# MicroSD-BoosterPack-RevA1.net
KiCad netlist of a schematic drawn in EAGLE
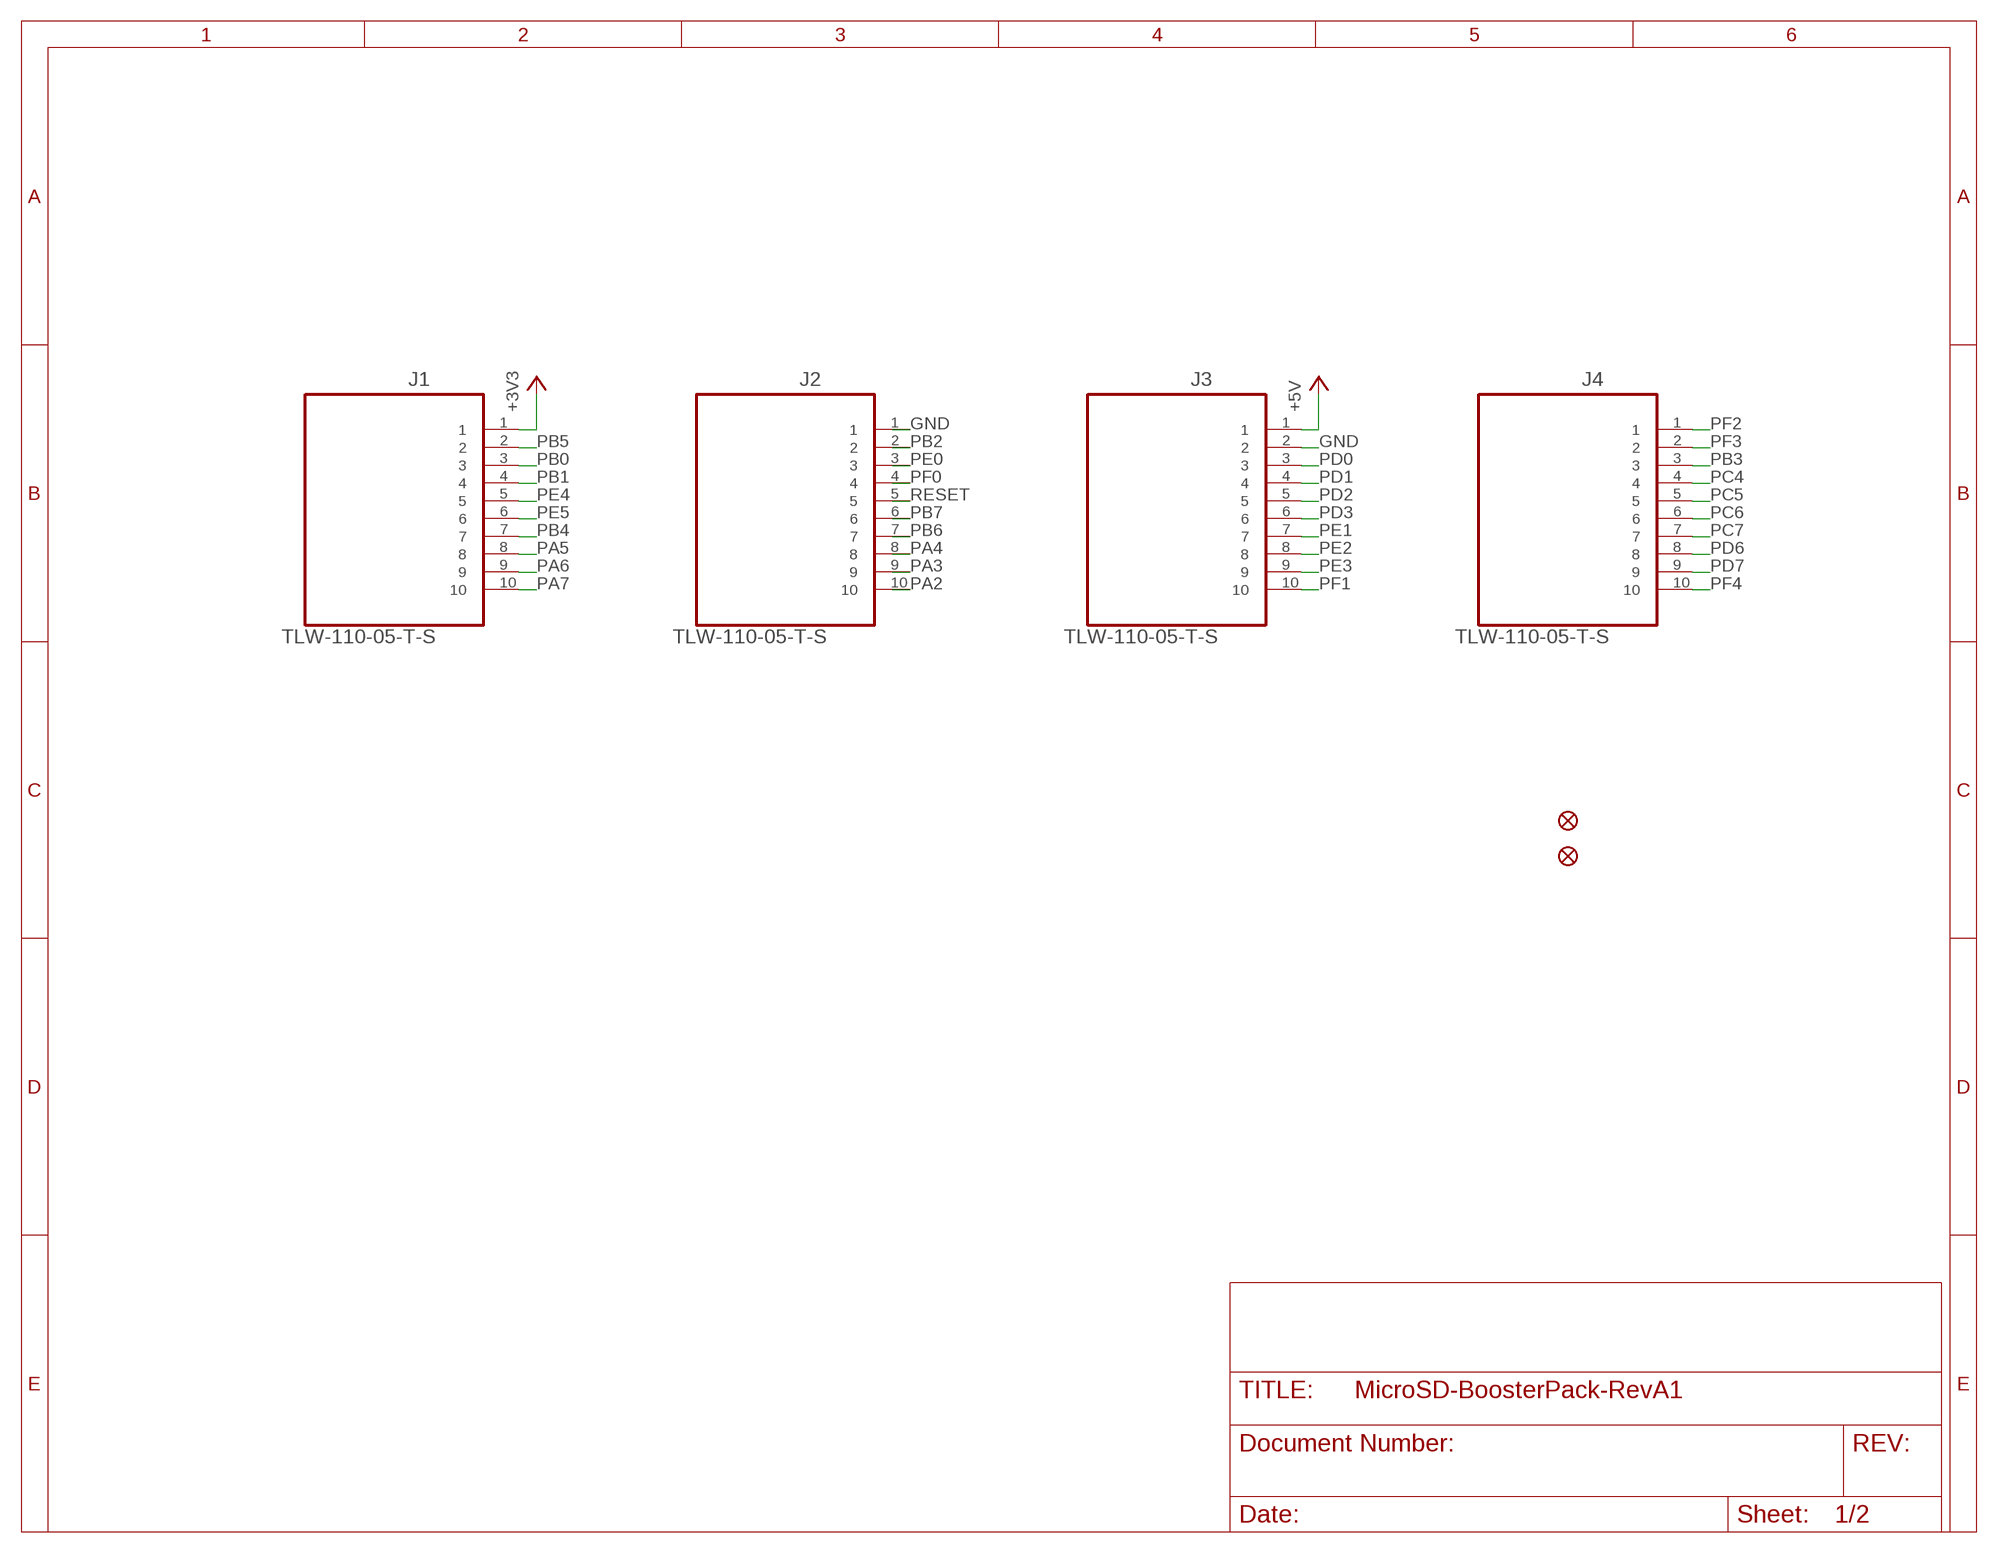
[diagram p0: schematic, sheet 1]
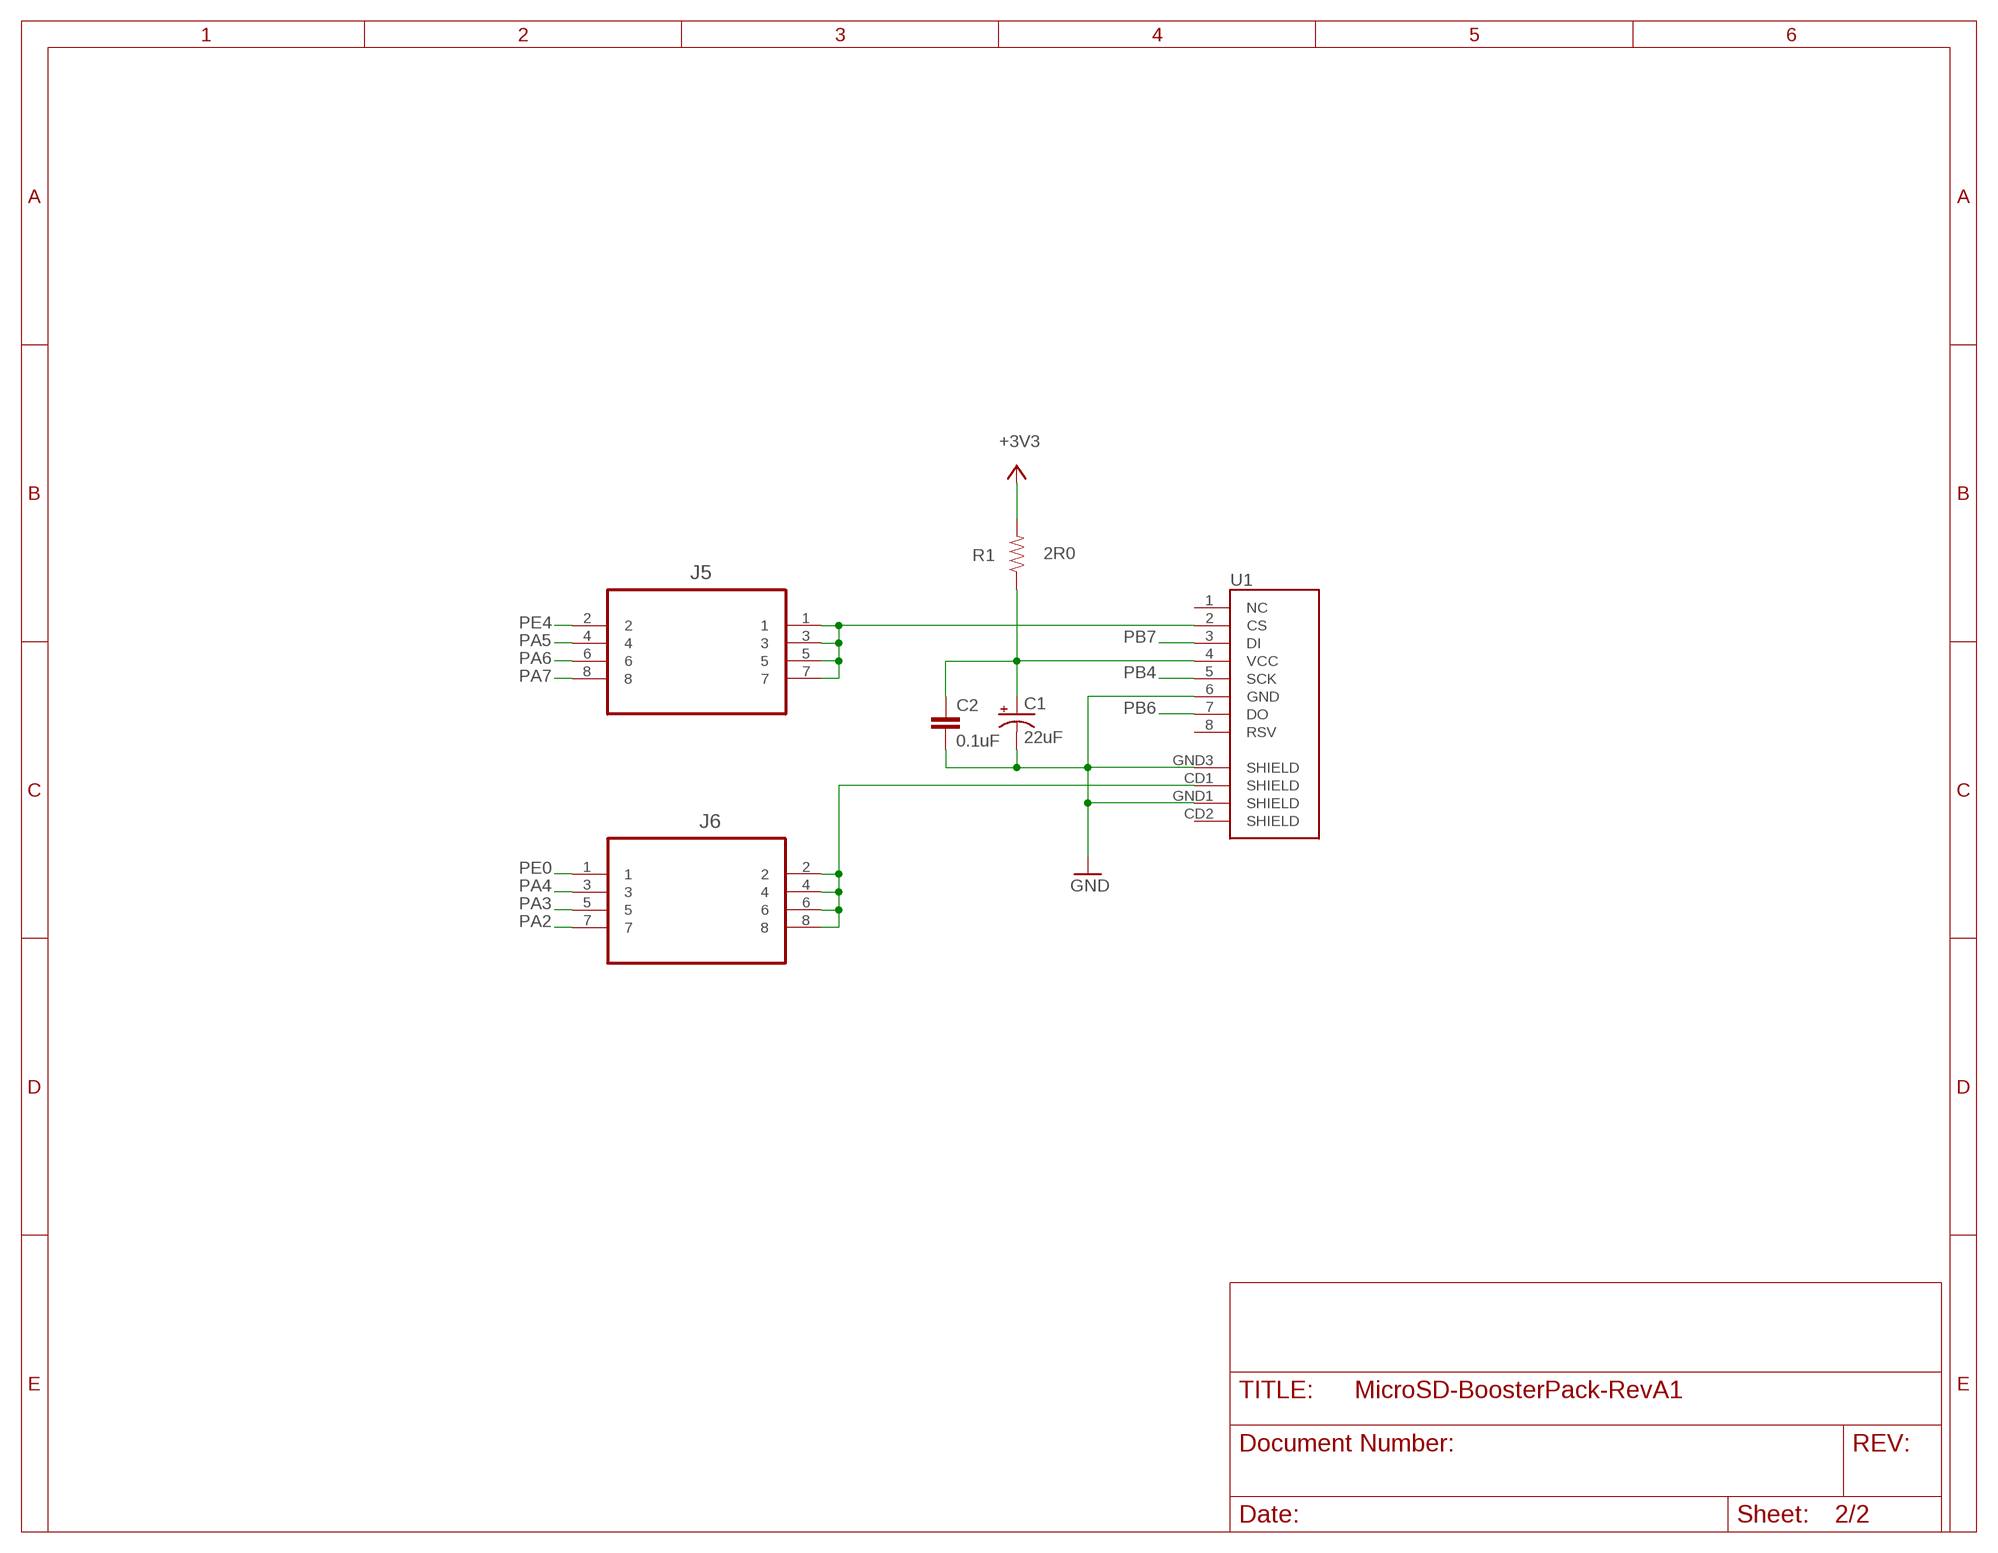
[diagram p1: schematic, sheet 2]

(export (version "E")
  (design (tool "Eeschema 10.0.6"))
  (components
    (comp (ref "C1")
      (value "22uF")
      (footprint "eagle-import:EIA3216")
      (libsource (lib "eagle-import") (part "10UF-16V-10%(TANT)"))
    )
    (comp (ref "C2")
      (value "0.1uF")
      (footprint "eagle-import:0603-CAP")
      (libsource (lib "eagle-import") (part "CAP0603-CAP"))
    )
    (comp (ref "J5")
      (value "SLW-104-01-T-D")
      (footprint "eagle-import:SAMTEC_SLW-104-01-T-D")
      (libsource (lib "eagle-import") (part "SLW-104-01-T-D"))
    )
    (comp (ref "J6")
      (value "SLW-104-01-T-D")
      (footprint "eagle-import:SAMTEC_SLW-104-01-T-D")
      (libsource (lib "eagle-import") (part "SLW-104-01-T-D"))
    )
    (comp (ref "R1")
      (value "2R0")
      (footprint "eagle-import:0603-RES")
      (libsource (lib "eagle-import") (part "RESISTOR0603-RES"))
    )
    (comp (ref "U1")
      (value "USD-SOCKETNEW")
      (footprint "eagle-import:MICRO-SD-SOCKET-PP")
      (libsource (lib "eagle-import") (part "USD-SOCKETNEW"))
    )
    (comp (ref "FID1")
      (value "FIDUCIAL1X2")
      (footprint "eagle-import:FIDUCIAL-1X2")
      (libsource (lib "eagle-import") (part "FIDUCIAL1X2"))
    )
    (comp (ref "FID2")
      (value "FIDUCIAL1X2")
      (footprint "eagle-import:FIDUCIAL-1X2")
      (libsource (lib "eagle-import") (part "FIDUCIAL1X2"))
    )
    (comp (ref "J1")
      (value "TLW-110-05-T-S")
      (footprint "eagle-import:SAMTEC_TLW-110-05-T-S")
      (libsource (lib "eagle-import") (part "TLW-110-05-T-S"))
    )
    (comp (ref "J2")
      (value "TLW-110-05-T-S")
      (footprint "eagle-import:SAMTEC_TLW-110-05-T-S")
      (fields
        (field (name "MPN") "TLW-110-05-T-S")
        (field (name "OC_FARNELL") "-")
        (field (name "OC_NEWARK") "12P0439")
        (field (name "PACKAGE") "CONN HEADER 10 POS .100 inch")
        (field (name "SUPPLIER") "SAMTEC")
      )
      (libsource (lib "eagle-import") (part "TLW-110-05-T-S"))
    )
    (comp (ref "J3")
      (value "TLW-110-05-T-S")
      (footprint "eagle-import:SAMTEC_TLW-110-05-T-S")
      (fields
        (field (name "MPN") "TLW-110-05-T-S")
        (field (name "OC_FARNELL") "-")
        (field (name "OC_NEWARK") "12P0439")
        (field (name "PACKAGE") "CONN HEADER 10 POS .100 inch")
        (field (name "SUPPLIER") "SAMTEC")
      )
      (libsource (lib "eagle-import") (part "TLW-110-05-T-S"))
    )
    (comp (ref "J4")
      (value "TLW-110-05-T-S")
      (footprint "eagle-import:SAMTEC_TLW-110-05-T-S")
      (fields
        (field (name "MPN") "TLW-110-05-T-S")
        (field (name "OC_FARNELL") "-")
        (field (name "OC_NEWARK") "12P0439")
        (field (name "PACKAGE") "CONN HEADER 10 POS .100 inch")
        (field (name "SUPPLIER") "SAMTEC")
      )
      (libsource (lib "eagle-import") (part "TLW-110-05-T-S"))
    )
  )
  (nets
    (net (code "1") (name "+3V3") (class "Default")
      (node (ref "J1") (pin "1") (pinfunction "1_1") (pintype "passive"))
      (node (ref "R1") (pin "2") (pinfunction "2_2") (pintype "passive"))
    )
    (net (code "2") (name "+5V") (class "Default")
      (node (ref "J3") (pin "1") (pinfunction "1_1") (pintype "passive"))
    )
    (net (code "3") (name "GND") (class "Default")
      (node (ref "C1") (pin "C") (pinfunction "-_C") (pintype "passive"))
      (node (ref "C2") (pin "2") (pinfunction "2_2") (pintype "passive"))
      (node (ref "J2") (pin "1") (pinfunction "1_1") (pintype "passive"))
      (node (ref "J3") (pin "2") (pinfunction "2_2") (pintype "passive"))
      (node (ref "U1") (pin "6") (pinfunction "GND_6") (pintype "bidirectional"))
      (node (ref "U1") (pin "GND1") (pinfunction "SHIELD_GND1") (pintype "bidirectional"))
      (node (ref "U1") (pin "GND3") (pinfunction "SHIELD_GND3") (pintype "bidirectional"))
    )
    (net (code "4") (name "Net-(C1-+)") (class "Default")
      (node (ref "C1") (pin "A") (pinfunction "+_A") (pintype "passive"))
      (node (ref "C2") (pin "1") (pinfunction "1_1") (pintype "passive"))
      (node (ref "R1") (pin "1") (pinfunction "1_1") (pintype "passive"))
      (node (ref "U1") (pin "4") (pinfunction "VCC_4") (pintype "bidirectional"))
    )
    (net (code "5") (name "Net-(J6-Pad2)") (class "Default")
      (node (ref "J6") (pin "2") (pinfunction "2_2") (pintype "passive"))
      (node (ref "J6") (pin "4") (pinfunction "4_4") (pintype "passive"))
      (node (ref "J6") (pin "6") (pinfunction "6_6") (pintype "passive"))
      (node (ref "J6") (pin "8") (pinfunction "8_8") (pintype "passive"))
      (node (ref "U1") (pin "CD1") (pinfunction "SHIELD_CD1") (pintype "bidirectional"))
    )
    (net (code "6") (name "Net-(U1-CS)") (class "Default")
      (node (ref "J5") (pin "1") (pinfunction "1_1") (pintype "passive"))
      (node (ref "J5") (pin "3") (pinfunction "3_3") (pintype "passive"))
      (node (ref "J5") (pin "5") (pinfunction "5_5") (pintype "passive"))
      (node (ref "J5") (pin "7") (pinfunction "7_7") (pintype "passive"))
      (node (ref "U1") (pin "2") (pinfunction "CS_2") (pintype "bidirectional"))
    )
    (net (code "7") (name "PA2") (class "Default")
      (node (ref "J2") (pin "10") (pinfunction "10_10") (pintype "passive"))
      (node (ref "J6") (pin "7") (pinfunction "7_7") (pintype "passive"))
    )
    (net (code "8") (name "PA3") (class "Default")
      (node (ref "J2") (pin "9") (pinfunction "9_9") (pintype "passive"))
      (node (ref "J6") (pin "5") (pinfunction "5_5") (pintype "passive"))
    )
    (net (code "9") (name "PA4") (class "Default")
      (node (ref "J2") (pin "8") (pinfunction "8_8") (pintype "passive"))
      (node (ref "J6") (pin "3") (pinfunction "3_3") (pintype "passive"))
    )
    (net (code "10") (name "PA5") (class "Default")
      (node (ref "J1") (pin "8") (pinfunction "8_8") (pintype "passive"))
      (node (ref "J5") (pin "4") (pinfunction "4_4") (pintype "passive"))
    )
    (net (code "11") (name "PA6") (class "Default")
      (node (ref "J1") (pin "9") (pinfunction "9_9") (pintype "passive"))
      (node (ref "J5") (pin "6") (pinfunction "6_6") (pintype "passive"))
    )
    (net (code "12") (name "PA7") (class "Default")
      (node (ref "J1") (pin "10") (pinfunction "10_10") (pintype "passive"))
      (node (ref "J5") (pin "8") (pinfunction "8_8") (pintype "passive"))
    )
    (net (code "13") (name "PB0") (class "Default")
      (node (ref "J1") (pin "3") (pinfunction "3_3") (pintype "passive"))
    )
    (net (code "14") (name "PB1") (class "Default")
      (node (ref "J1") (pin "4") (pinfunction "4_4") (pintype "passive"))
    )
    (net (code "15") (name "PB2") (class "Default")
      (node (ref "J2") (pin "2") (pinfunction "2_2") (pintype "passive"))
    )
    (net (code "16") (name "PB3") (class "Default")
      (node (ref "J4") (pin "3") (pinfunction "3_3") (pintype "passive"))
    )
    (net (code "17") (name "PB4") (class "Default")
      (node (ref "J1") (pin "7") (pinfunction "7_7") (pintype "passive"))
      (node (ref "U1") (pin "5") (pinfunction "SCK_5") (pintype "bidirectional"))
    )
    (net (code "18") (name "PB5") (class "Default")
      (node (ref "J1") (pin "2") (pinfunction "2_2") (pintype "passive"))
    )
    (net (code "19") (name "PB6") (class "Default")
      (node (ref "J2") (pin "7") (pinfunction "7_7") (pintype "passive"))
      (node (ref "U1") (pin "7") (pinfunction "DO_7") (pintype "bidirectional"))
    )
    (net (code "20") (name "PB7") (class "Default")
      (node (ref "J2") (pin "6") (pinfunction "6_6") (pintype "passive"))
      (node (ref "U1") (pin "3") (pinfunction "DI_3") (pintype "bidirectional"))
    )
    (net (code "21") (name "PC4") (class "Default")
      (node (ref "J4") (pin "4") (pinfunction "4_4") (pintype "passive"))
    )
    (net (code "22") (name "PC5") (class "Default")
      (node (ref "J4") (pin "5") (pinfunction "5_5") (pintype "passive"))
    )
    (net (code "23") (name "PC6") (class "Default")
      (node (ref "J4") (pin "6") (pinfunction "6_6") (pintype "passive"))
    )
    (net (code "24") (name "PC7") (class "Default")
      (node (ref "J4") (pin "7") (pinfunction "7_7") (pintype "passive"))
    )
    (net (code "25") (name "PD0") (class "Default")
      (node (ref "J3") (pin "3") (pinfunction "3_3") (pintype "passive"))
    )
    (net (code "26") (name "PD1") (class "Default")
      (node (ref "J3") (pin "4") (pinfunction "4_4") (pintype "passive"))
    )
    (net (code "27") (name "PD2") (class "Default")
      (node (ref "J3") (pin "5") (pinfunction "5_5") (pintype "passive"))
    )
    (net (code "28") (name "PD3") (class "Default")
      (node (ref "J3") (pin "6") (pinfunction "6_6") (pintype "passive"))
    )
    (net (code "29") (name "PD6") (class "Default")
      (node (ref "J4") (pin "8") (pinfunction "8_8") (pintype "passive"))
    )
    (net (code "30") (name "PD7") (class "Default")
      (node (ref "J4") (pin "9") (pinfunction "9_9") (pintype "passive"))
    )
    (net (code "31") (name "PE0") (class "Default")
      (node (ref "J2") (pin "3") (pinfunction "3_3") (pintype "passive"))
      (node (ref "J6") (pin "1") (pinfunction "1_1") (pintype "passive"))
    )
    (net (code "32") (name "PE1") (class "Default")
      (node (ref "J3") (pin "7") (pinfunction "7_7") (pintype "passive"))
    )
    (net (code "33") (name "PE2") (class "Default")
      (node (ref "J3") (pin "8") (pinfunction "8_8") (pintype "passive"))
    )
    (net (code "34") (name "PE3") (class "Default")
      (node (ref "J3") (pin "9") (pinfunction "9_9") (pintype "passive"))
    )
    (net (code "35") (name "PE4") (class "Default")
      (node (ref "J1") (pin "5") (pinfunction "5_5") (pintype "passive"))
      (node (ref "J5") (pin "2") (pinfunction "2_2") (pintype "passive"))
    )
    (net (code "36") (name "PE5") (class "Default")
      (node (ref "J1") (pin "6") (pinfunction "6_6") (pintype "passive"))
    )
    (net (code "37") (name "PF0") (class "Default")
      (node (ref "J2") (pin "4") (pinfunction "4_4") (pintype "passive"))
    )
    (net (code "38") (name "PF1") (class "Default")
      (node (ref "J3") (pin "10") (pinfunction "10_10") (pintype "passive"))
    )
    (net (code "39") (name "PF2") (class "Default")
      (node (ref "J4") (pin "1") (pinfunction "1_1") (pintype "passive"))
    )
    (net (code "40") (name "PF3") (class "Default")
      (node (ref "J4") (pin "2") (pinfunction "2_2") (pintype "passive"))
    )
    (net (code "41") (name "PF4") (class "Default")
      (node (ref "J4") (pin "10") (pinfunction "10_10") (pintype "passive"))
    )
    (net (code "42") (name "RESET") (class "Default")
      (node (ref "J2") (pin "5") (pinfunction "5_5") (pintype "passive"))
    )
    (net (code "43") (name "unconnected-(U1-NC-Pad1)") (class "Default")
      (node (ref "U1") (pin "1") (pinfunction "NC_1") (pintype "bidirectional"))
    )
    (net (code "44") (name "unconnected-(U1-RSV-Pad8)") (class "Default")
      (node (ref "U1") (pin "8") (pinfunction "RSV_8") (pintype "bidirectional"))
    )
    (net (code "45") (name "unconnected-(U1-SHIELD-PadCD2)") (class "Default")
      (node (ref "U1") (pin "CD2") (pinfunction "SHIELD_CD2") (pintype "bidirectional"))
    )
  )
)
